# a4989_smoothiebrain_daughterboard.net
KiCad netlist of a schematic drawn in EAGLE
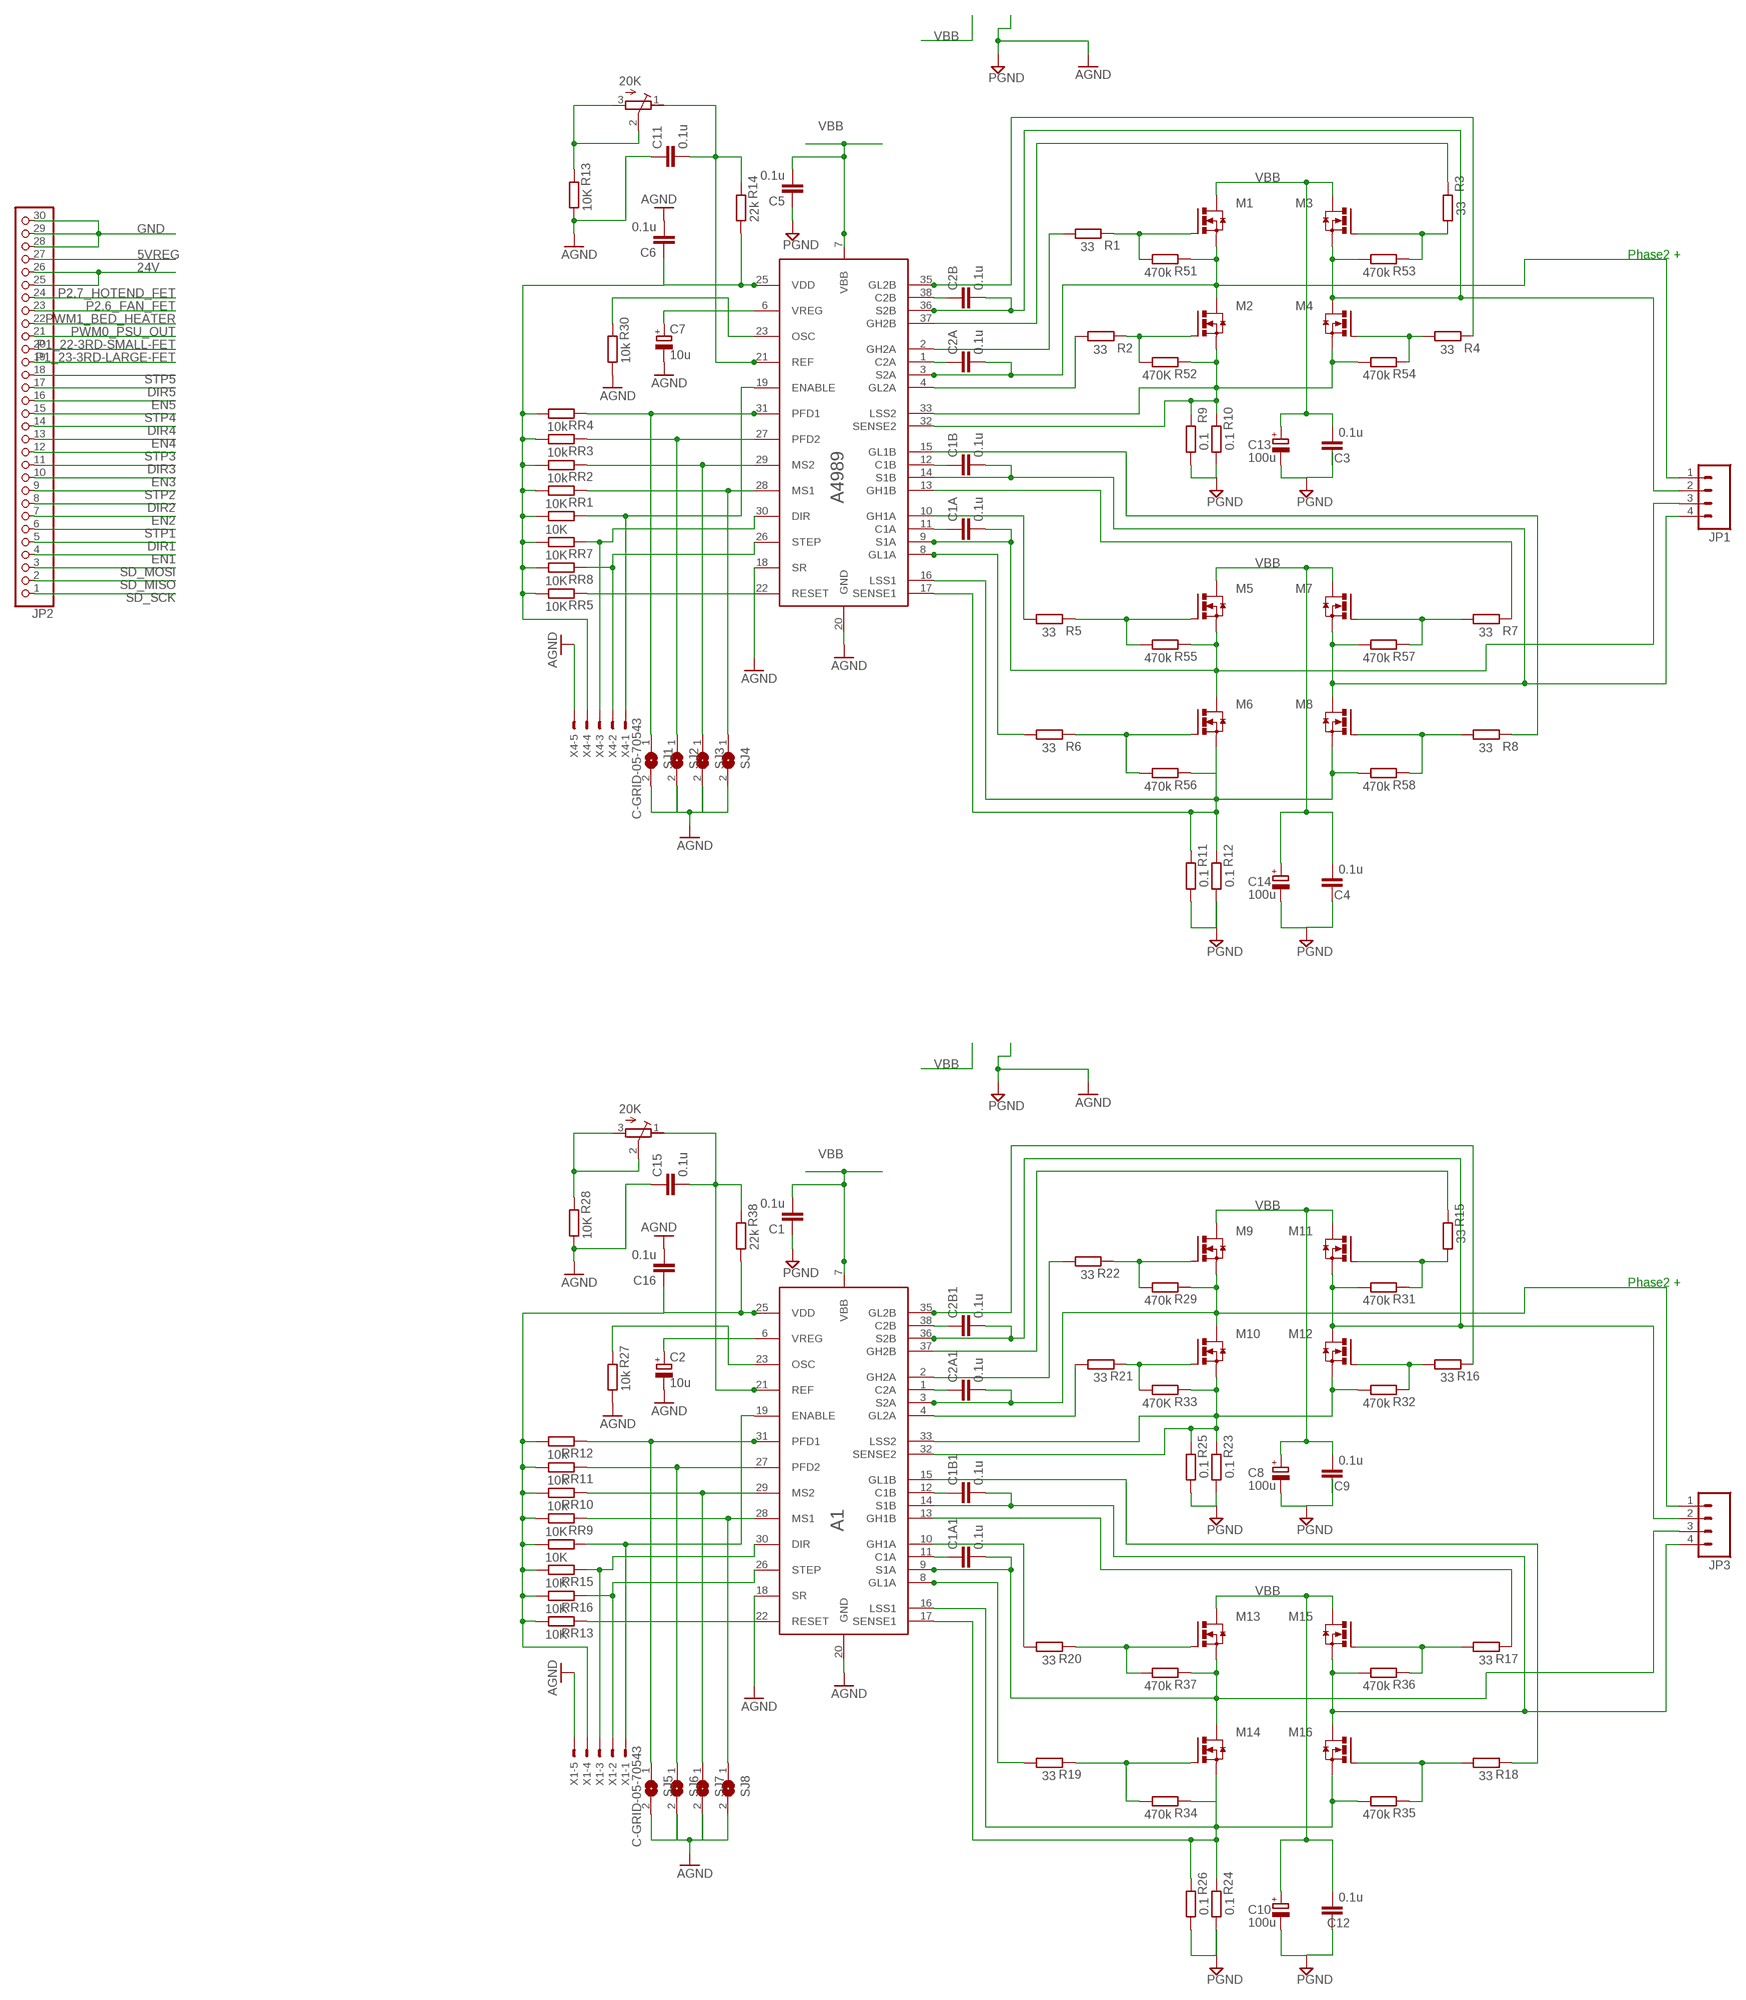
[diagram p0: schematic, sheet 1]

(export (version "E")
  (design (tool "Eeschema 10.0.6"))
  (components
    (comp (ref "A1")
      (value "A4989")
      (footprint "eagle-import:TSSOP39")
      (libsource (lib "eagle-import") (part "A4989"))
    )
    (comp (ref "A4989")
      (value "A4989")
      (footprint "eagle-import:TSSOP39")
      (libsource (lib "eagle-import") (part "A4989"))
    )
    (comp (ref "C1")
      (value "0.1u")
      (footprint "eagle-import:C0603")
      (libsource (lib "eagle-import") (part "C-EUC0603"))
    )
    (comp (ref "C1A")
      (value "0.1u")
      (footprint "eagle-import:C0603")
      (libsource (lib "eagle-import") (part "C-EUC0603"))
    )
    (comp (ref "C1A1")
      (value "0.1u")
      (footprint "eagle-import:C0603")
      (libsource (lib "eagle-import") (part "C-EUC0603"))
    )
    (comp (ref "C1B")
      (value "0.1u")
      (footprint "eagle-import:C0603")
      (libsource (lib "eagle-import") (part "C-EUC0603"))
    )
    (comp (ref "C1B1")
      (value "0.1u")
      (footprint "eagle-import:C0603")
      (libsource (lib "eagle-import") (part "C-EUC0603"))
    )
    (comp (ref "C2")
      (value "10u")
      (footprint "eagle-import:153CLV-0605")
      (libsource (lib "eagle-import") (part "CPOL-EU153CLV-0605"))
    )
    (comp (ref "C2A")
      (value "0.1u")
      (footprint "eagle-import:C0603")
      (libsource (lib "eagle-import") (part "C-EUC0603"))
    )
    (comp (ref "C2A1")
      (value "0.1u")
      (footprint "eagle-import:C0603")
      (libsource (lib "eagle-import") (part "C-EUC0603"))
    )
    (comp (ref "C2B")
      (value "0.1u")
      (footprint "eagle-import:C0603")
      (libsource (lib "eagle-import") (part "C-EUC0603"))
    )
    (comp (ref "C2B1")
      (value "0.1u")
      (footprint "eagle-import:C0603")
      (libsource (lib "eagle-import") (part "C-EUC0603"))
    )
    (comp (ref "C3")
      (value "0.1u")
      (footprint "eagle-import:C0603")
      (libsource (lib "eagle-import") (part "C-EUC0603"))
    )
    (comp (ref "C4")
      (value "0.1u")
      (footprint "eagle-import:C0603")
      (libsource (lib "eagle-import") (part "C-EUC0603"))
    )
    (comp (ref "C5")
      (value "0.1u")
      (footprint "eagle-import:C0603")
      (libsource (lib "eagle-import") (part "C-EUC0603"))
    )
    (comp (ref "C6")
      (value "0.1u")
      (footprint "eagle-import:C0603")
      (libsource (lib "eagle-import") (part "C-EUC0603"))
    )
    (comp (ref "C7")
      (value "10u")
      (footprint "eagle-import:153CLV-0605")
      (libsource (lib "eagle-import") (part "CPOL-EU153CLV-0605"))
    )
    (comp (ref "C8")
      (value "100u")
      (footprint "eagle-import:E5-10,5")
      (libsource (lib "eagle-import") (part "CPOL-EUE5-10.5"))
    )
    (comp (ref "C9")
      (value "0.1u")
      (footprint "eagle-import:C0603")
      (libsource (lib "eagle-import") (part "C-EUC0603"))
    )
    (comp (ref "C10")
      (value "100u")
      (footprint "eagle-import:E5-10,5")
      (libsource (lib "eagle-import") (part "CPOL-EUE5-10.5"))
    )
    (comp (ref "C11")
      (value "0.1u")
      (footprint "eagle-import:C0603")
      (libsource (lib "eagle-import") (part "C-EUC0603"))
    )
    (comp (ref "C12")
      (value "0.1u")
      (footprint "eagle-import:C0603")
      (libsource (lib "eagle-import") (part "C-EUC0603"))
    )
    (comp (ref "C13")
      (value "100u")
      (footprint "eagle-import:E5-10,5")
      (libsource (lib "eagle-import") (part "CPOL-EUE5-10.5"))
    )
    (comp (ref "C14")
      (value "100u")
      (footprint "eagle-import:E5-10,5")
      (libsource (lib "eagle-import") (part "CPOL-EUE5-10.5"))
    )
    (comp (ref "C15")
      (value "0.1u")
      (footprint "eagle-import:C0603")
      (libsource (lib "eagle-import") (part "C-EUC0603"))
    )
    (comp (ref "C16")
      (value "0.1u")
      (footprint "eagle-import:C0603")
      (libsource (lib "eagle-import") (part "C-EUC0603"))
    )
    (comp (ref "JP1")
      (value "M04SCREW")
      (footprint "eagle-import:SCREWTERMINAL-3.5MM-4")
      (libsource (lib "eagle-import") (part "M04SCREW"))
    )
    (comp (ref "JP2")
      (value "PINHD-1X30")
      (footprint "eagle-import:1X30")
      (libsource (lib "eagle-import") (part "PINHD-1X30"))
    )
    (comp (ref "JP3")
      (value "M04SCREW")
      (footprint "eagle-import:SCREWTERMINAL-3.5MM-4")
      (libsource (lib "eagle-import") (part "M04SCREW"))
    )
    (comp (ref "M1")
      (value "IRLR024N")
      (footprint "eagle-import:TO252")
      (libsource (lib "eagle-import") (part "IRLR024N"))
    )
    (comp (ref "M2")
      (value "IRLR024N")
      (footprint "eagle-import:TO252")
      (libsource (lib "eagle-import") (part "IRLR024N"))
    )
    (comp (ref "M3")
      (value "IRLR024N")
      (footprint "eagle-import:TO252")
      (libsource (lib "eagle-import") (part "IRLR024N"))
    )
    (comp (ref "M4")
      (value "IRLR024N")
      (footprint "eagle-import:TO252")
      (libsource (lib "eagle-import") (part "IRLR024N"))
    )
    (comp (ref "M5")
      (value "IRLR024N")
      (footprint "eagle-import:TO252")
      (libsource (lib "eagle-import") (part "IRLR024N"))
    )
    (comp (ref "M6")
      (value "IRLR024N")
      (footprint "eagle-import:TO252")
      (libsource (lib "eagle-import") (part "IRLR024N"))
    )
    (comp (ref "M7")
      (value "IRLR024N")
      (footprint "eagle-import:TO252")
      (libsource (lib "eagle-import") (part "IRLR024N"))
    )
    (comp (ref "M8")
      (value "IRLR024N")
      (footprint "eagle-import:TO252")
      (libsource (lib "eagle-import") (part "IRLR024N"))
    )
    (comp (ref "M9")
      (value "IRLR024N")
      (footprint "eagle-import:TO252")
      (libsource (lib "eagle-import") (part "IRLR024N"))
    )
    (comp (ref "M10")
      (value "IRLR024N")
      (footprint "eagle-import:TO252")
      (libsource (lib "eagle-import") (part "IRLR024N"))
    )
    (comp (ref "M11")
      (value "IRLR024N")
      (footprint "eagle-import:TO252")
      (libsource (lib "eagle-import") (part "IRLR024N"))
    )
    (comp (ref "M12")
      (value "IRLR024N")
      (footprint "eagle-import:TO252")
      (libsource (lib "eagle-import") (part "IRLR024N"))
    )
    (comp (ref "M13")
      (value "IRLR024N")
      (footprint "eagle-import:TO252")
      (libsource (lib "eagle-import") (part "IRLR024N"))
    )
    (comp (ref "M14")
      (value "IRLR024N")
      (footprint "eagle-import:TO252")
      (libsource (lib "eagle-import") (part "IRLR024N"))
    )
    (comp (ref "M15")
      (value "IRLR024N")
      (footprint "eagle-import:TO252")
      (libsource (lib "eagle-import") (part "IRLR024N"))
    )
    (comp (ref "M16")
      (value "IRLR024N")
      (footprint "eagle-import:TO252")
      (libsource (lib "eagle-import") (part "IRLR024N"))
    )
    (comp (ref "R1")
      (value "33")
      (footprint "eagle-import:R0603")
      (libsource (lib "eagle-import") (part "R-EU_R0603"))
    )
    (comp (ref "R2")
      (value "33")
      (footprint "eagle-import:R0603")
      (libsource (lib "eagle-import") (part "R-EU_R0603"))
    )
    (comp (ref "R3")
      (value "33")
      (footprint "eagle-import:R0603")
      (libsource (lib "eagle-import") (part "R-EU_R0603"))
    )
    (comp (ref "R4")
      (value "33")
      (footprint "eagle-import:R0603")
      (libsource (lib "eagle-import") (part "R-EU_R0603"))
    )
    (comp (ref "R5")
      (value "33")
      (footprint "eagle-import:R0603")
      (libsource (lib "eagle-import") (part "R-EU_R0603"))
    )
    (comp (ref "R6")
      (value "33")
      (footprint "eagle-import:R0603")
      (libsource (lib "eagle-import") (part "R-EU_R0603"))
    )
    (comp (ref "R7")
      (value "33")
      (footprint "eagle-import:R0603")
      (libsource (lib "eagle-import") (part "R-EU_R0603"))
    )
    (comp (ref "R8")
      (value "33")
      (footprint "eagle-import:R0603")
      (libsource (lib "eagle-import") (part "R-EU_R0603"))
    )
    (comp (ref "R9")
      (value "0.1")
      (footprint "eagle-import:R2512")
      (libsource (lib "eagle-import") (part "R-EU_R2512"))
    )
    (comp (ref "R10")
      (value "0.1")
      (footprint "eagle-import:R2512")
      (libsource (lib "eagle-import") (part "R-EU_R2512"))
    )
    (comp (ref "R11")
      (value "0.1")
      (footprint "eagle-import:R2512")
      (libsource (lib "eagle-import") (part "R-EU_R2512"))
    )
    (comp (ref "R12")
      (value "0.1")
      (footprint "eagle-import:R2512")
      (libsource (lib "eagle-import") (part "R-EU_R2512"))
    )
    (comp (ref "R13")
      (value "10K")
      (footprint "eagle-import:R0603")
      (libsource (lib "eagle-import") (part "R-EU_R0603"))
    )
    (comp (ref "R14")
      (value "22k")
      (footprint "eagle-import:R0603")
      (libsource (lib "eagle-import") (part "R-EU_R0603"))
    )
    (comp (ref "R15")
      (value "33")
      (footprint "eagle-import:R0603")
      (libsource (lib "eagle-import") (part "R-EU_R0603"))
    )
    (comp (ref "R16")
      (value "33")
      (footprint "eagle-import:R0603")
      (libsource (lib "eagle-import") (part "R-EU_R0603"))
    )
    (comp (ref "R17")
      (value "33")
      (footprint "eagle-import:R0603")
      (libsource (lib "eagle-import") (part "R-EU_R0603"))
    )
    (comp (ref "R18")
      (value "33")
      (footprint "eagle-import:R0603")
      (libsource (lib "eagle-import") (part "R-EU_R0603"))
    )
    (comp (ref "R19")
      (value "33")
      (footprint "eagle-import:R0603")
      (libsource (lib "eagle-import") (part "R-EU_R0603"))
    )
    (comp (ref "R20")
      (value "33")
      (footprint "eagle-import:R0603")
      (libsource (lib "eagle-import") (part "R-EU_R0603"))
    )
    (comp (ref "R21")
      (value "33")
      (footprint "eagle-import:R0603")
      (libsource (lib "eagle-import") (part "R-EU_R0603"))
    )
    (comp (ref "R22")
      (value "33")
      (footprint "eagle-import:R0603")
      (libsource (lib "eagle-import") (part "R-EU_R0603"))
    )
    (comp (ref "R23")
      (value "0.1")
      (footprint "eagle-import:R2512")
      (libsource (lib "eagle-import") (part "R-EU_R2512"))
    )
    (comp (ref "R24")
      (value "0.1")
      (footprint "eagle-import:R2512")
      (libsource (lib "eagle-import") (part "R-EU_R2512"))
    )
    (comp (ref "R25")
      (value "0.1")
      (footprint "eagle-import:R2512")
      (libsource (lib "eagle-import") (part "R-EU_R2512"))
    )
    (comp (ref "R26")
      (value "0.1")
      (footprint "eagle-import:R2512")
      (libsource (lib "eagle-import") (part "R-EU_R2512"))
    )
    (comp (ref "R27")
      (value "10k")
      (footprint "eagle-import:R0603")
      (libsource (lib "eagle-import") (part "R-EU_R0603"))
    )
    (comp (ref "R28")
      (value "10K")
      (footprint "eagle-import:R0603")
      (libsource (lib "eagle-import") (part "R-EU_R0603"))
    )
    (comp (ref "R29")
      (value "470k")
      (footprint "eagle-import:R0603")
      (libsource (lib "eagle-import") (part "R-EU_R0603"))
    )
    (comp (ref "R30")
      (value "10k")
      (footprint "eagle-import:R0603")
      (libsource (lib "eagle-import") (part "R-EU_R0603"))
    )
    (comp (ref "R31")
      (value "470k")
      (footprint "eagle-import:R0603")
      (libsource (lib "eagle-import") (part "R-EU_R0603"))
    )
    (comp (ref "R32")
      (value "470k")
      (footprint "eagle-import:R0603")
      (libsource (lib "eagle-import") (part "R-EU_R0603"))
    )
    (comp (ref "R33")
      (value "470K")
      (footprint "eagle-import:R0603")
      (libsource (lib "eagle-import") (part "R-EU_R0603"))
    )
    (comp (ref "R34")
      (value "470k")
      (footprint "eagle-import:R0603")
      (libsource (lib "eagle-import") (part "R-EU_R0603"))
    )
    (comp (ref "R35")
      (value "470k")
      (footprint "eagle-import:R0603")
      (libsource (lib "eagle-import") (part "R-EU_R0603"))
    )
    (comp (ref "R36")
      (value "470k")
      (footprint "eagle-import:R0603")
      (libsource (lib "eagle-import") (part "R-EU_R0603"))
    )
    (comp (ref "R37")
      (value "470k")
      (footprint "eagle-import:R0603")
      (libsource (lib "eagle-import") (part "R-EU_R0603"))
    )
    (comp (ref "R38")
      (value "22k")
      (footprint "eagle-import:R0603")
      (libsource (lib "eagle-import") (part "R-EU_R0603"))
    )
    (comp (ref "R51")
      (value "470k")
      (footprint "eagle-import:R0603")
      (libsource (lib "eagle-import") (part "R-EU_R0603"))
    )
    (comp (ref "R52")
      (value "470K")
      (footprint "eagle-import:R0603")
      (libsource (lib "eagle-import") (part "R-EU_R0603"))
    )
    (comp (ref "R53")
      (value "470k")
      (footprint "eagle-import:R0603")
      (libsource (lib "eagle-import") (part "R-EU_R0603"))
    )
    (comp (ref "R54")
      (value "470k")
      (footprint "eagle-import:R0603")
      (libsource (lib "eagle-import") (part "R-EU_R0603"))
    )
    (comp (ref "R55")
      (value "470k")
      (footprint "eagle-import:R0603")
      (libsource (lib "eagle-import") (part "R-EU_R0603"))
    )
    (comp (ref "R56")
      (value "470k")
      (footprint "eagle-import:R0603")
      (libsource (lib "eagle-import") (part "R-EU_R0603"))
    )
    (comp (ref "R57")
      (value "470k")
      (footprint "eagle-import:R0603")
      (libsource (lib "eagle-import") (part "R-EU_R0603"))
    )
    (comp (ref "R58")
      (value "470k")
      (footprint "eagle-import:R0603")
      (libsource (lib "eagle-import") (part "R-EU_R0603"))
    )
    (comp (ref "RR1")
      (value "10K")
      (footprint "eagle-import:R0603")
      (libsource (lib "eagle-import") (part "R-EU_R0603"))
    )
    (comp (ref "RR2")
      (value "10k")
      (footprint "eagle-import:R0603")
      (libsource (lib "eagle-import") (part "R-EU_R0603"))
    )
    (comp (ref "RR3")
      (value "10k")
      (footprint "eagle-import:R0603")
      (libsource (lib "eagle-import") (part "R-EU_R0603"))
    )
    (comp (ref "RR4")
      (value "10k")
      (footprint "eagle-import:R0603")
      (libsource (lib "eagle-import") (part "R-EU_R0603"))
    )
    (comp (ref "RR5")
      (value "10K")
      (footprint "eagle-import:R0603")
      (libsource (lib "eagle-import") (part "R-EU_R0603"))
    )
    (comp (ref "RR6")
      (value "10K")
      (footprint "eagle-import:R0603")
      (libsource (lib "eagle-import") (part "R-EU_R0603"))
    )
    (comp (ref "RR7")
      (value "10K")
      (footprint "eagle-import:R0603")
      (libsource (lib "eagle-import") (part "R-EU_R0603"))
    )
    (comp (ref "RR8")
      (value "10K")
      (footprint "eagle-import:R0603")
      (libsource (lib "eagle-import") (part "R-EU_R0603"))
    )
    (comp (ref "RR9")
      (value "10K")
      (footprint "eagle-import:R0603")
      (libsource (lib "eagle-import") (part "R-EU_R0603"))
    )
    (comp (ref "RR10")
      (value "10k")
      (footprint "eagle-import:R0603")
      (libsource (lib "eagle-import") (part "R-EU_R0603"))
    )
    (comp (ref "RR11")
      (value "10k")
      (footprint "eagle-import:R0603")
      (libsource (lib "eagle-import") (part "R-EU_R0603"))
    )
    (comp (ref "RR12")
      (value "10k")
      (footprint "eagle-import:R0603")
      (libsource (lib "eagle-import") (part "R-EU_R0603"))
    )
    (comp (ref "RR13")
      (value "10K")
      (footprint "eagle-import:R0603")
      (libsource (lib "eagle-import") (part "R-EU_R0603"))
    )
    (comp (ref "RR14")
      (value "10K")
      (footprint "eagle-import:R0603")
      (libsource (lib "eagle-import") (part "R-EU_R0603"))
    )
    (comp (ref "RR15")
      (value "10K")
      (footprint "eagle-import:R0603")
      (libsource (lib "eagle-import") (part "R-EU_R0603"))
    )
    (comp (ref "RR16")
      (value "10K")
      (footprint "eagle-import:R0603")
      (libsource (lib "eagle-import") (part "R-EU_R0603"))
    )
    (comp (ref "SJ1") (value "SJ") (footprint "eagle-import:SJ") (libsource (lib "eagle-import") (part "SJ")))
    (comp (ref "SJ2") (value "SJ") (footprint "eagle-import:SJ") (libsource (lib "eagle-import") (part "SJ")))
    (comp (ref "SJ3") (value "SJ") (footprint "eagle-import:SJ") (libsource (lib "eagle-import") (part "SJ")))
    (comp (ref "SJ4") (value "SJ") (footprint "eagle-import:SJ") (libsource (lib "eagle-import") (part "SJ")))
    (comp (ref "SJ5") (value "SJ") (footprint "eagle-import:SJ") (libsource (lib "eagle-import") (part "SJ")))
    (comp (ref "SJ6") (value "SJ") (footprint "eagle-import:SJ") (libsource (lib "eagle-import") (part "SJ")))
    (comp (ref "SJ7") (value "SJ") (footprint "eagle-import:SJ") (libsource (lib "eagle-import") (part "SJ")))
    (comp (ref "SJ8") (value "SJ") (footprint "eagle-import:SJ") (libsource (lib "eagle-import") (part "SJ")))
    (comp (ref "U$1")
      (value "20K")
      (footprint "eagle-import:BOURNS_3266W")
      (libsource (lib "eagle-import") (part "BOURNS_TRIMMER_3266W"))
    )
    (comp (ref "U$2")
      (value "20K")
      (footprint "eagle-import:BOURNS_3266W")
      (libsource (lib "eagle-import") (part "BOURNS_TRIMMER_3266W"))
    )
    (comp (ref "X1")
      (value "C-GRID-05-70543")
      (footprint "eagle-import:70543-05")
      (libsource (lib "eagle-import") (part "C-GRID-05-70543"))
    )
    (comp (ref "X4")
      (value "C-GRID-05-70543")
      (footprint "eagle-import:70543-05")
      (libsource (lib "eagle-import") (part "C-GRID-05-70543"))
    )
  )
  (nets
    (net (code "1") (name "/5VREG") (class "Default")
      (node (ref "A4989") (pin "25") (pinfunction "VDD_25") (pintype "bidirectional"))
      (node (ref "C6") (pin "1") (pinfunction "1_1") (pintype "passive"))
      (node (ref "JP2") (pin "27") (pinfunction "27_27") (pintype "passive"))
      (node (ref "R14") (pin "2") (pinfunction "2_2") (pintype "passive"))
      (node (ref "RR1") (pin "2") (pinfunction "2_2") (pintype "passive"))
      (node (ref "RR2") (pin "2") (pinfunction "2_2") (pintype "passive"))
      (node (ref "RR3") (pin "2") (pinfunction "2_2") (pintype "passive"))
      (node (ref "RR4") (pin "2") (pinfunction "2_2") (pintype "passive"))
      (node (ref "RR5") (pin "2") (pinfunction "2_2") (pintype "passive"))
      (node (ref "RR6") (pin "2") (pinfunction "2_2") (pintype "passive"))
      (node (ref "RR7") (pin "2") (pinfunction "2_2") (pintype "passive"))
      (node (ref "RR8") (pin "2") (pinfunction "2_2") (pintype "passive"))
      (node (ref "X4") (pin "4") (pinfunction "S_4") (pintype "passive"))
    )
    (net (code "2") (name "/24V") (class "Default")
      (node (ref "JP2") (pin "25") (pinfunction "25_25") (pintype "passive"))
      (node (ref "JP2") (pin "26") (pinfunction "26_26") (pintype "passive"))
    )
    (net (code "3") (name "/DIR1") (class "Default")
      (node (ref "A4989") (pin "30") (pinfunction "DIR_30") (pintype "bidirectional"))
      (node (ref "JP2") (pin "5") (pinfunction "5_5") (pintype "passive"))
      (node (ref "RR7") (pin "1") (pinfunction "1_1") (pintype "passive"))
      (node (ref "X4") (pin "3") (pinfunction "S_3") (pintype "passive"))
    )
    (net (code "4") (name "/DIR2") (class "Default")
      (node (ref "JP2") (pin "8") (pinfunction "8_8") (pintype "passive"))
    )
    (net (code "5") (name "/DIR3") (class "Default")
      (node (ref "JP2") (pin "11") (pinfunction "11_11") (pintype "passive"))
    )
    (net (code "6") (name "/DIR4") (class "Default")
      (node (ref "JP2") (pin "14") (pinfunction "14_14") (pintype "passive"))
    )
    (net (code "7") (name "/DIR5") (class "Default")
      (node (ref "JP2") (pin "17") (pinfunction "17_17") (pintype "passive"))
    )
    (net (code "8") (name "/EN1") (class "Default")
      (node (ref "A4989") (pin "19") (pinfunction "ENABLE_19") (pintype "bidirectional"))
      (node (ref "JP2") (pin "4") (pinfunction "4_4") (pintype "passive"))
      (node (ref "RR6") (pin "1") (pinfunction "1_1") (pintype "passive"))
      (node (ref "X4") (pin "1") (pinfunction "S_1") (pintype "passive"))
    )
    (net (code "9") (name "/EN2") (class "Default")
      (node (ref "JP2") (pin "7") (pinfunction "7_7") (pintype "passive"))
    )
    (net (code "10") (name "/EN3") (class "Default")
      (node (ref "JP2") (pin "10") (pinfunction "10_10") (pintype "passive"))
    )
    (net (code "11") (name "/EN4") (class "Default")
      (node (ref "JP2") (pin "13") (pinfunction "13_13") (pintype "passive"))
    )
    (net (code "12") (name "/EN5") (class "Default")
      (node (ref "JP2") (pin "16") (pinfunction "16_16") (pintype "passive"))
    )
    (net (code "13") (name "/P1_22-3RD-SMALL-FET") (class "Default")
      (node (ref "JP2") (pin "20") (pinfunction "20_20") (pintype "passive"))
    )
    (net (code "14") (name "/P1_23-3RD-LARGE-FET") (class "Default")
      (node (ref "JP2") (pin "19") (pinfunction "19_19") (pintype "passive"))
    )
    (net (code "15") (name "/P2.6_FAN_FET") (class "Default")
      (node (ref "JP2") (pin "23") (pinfunction "23_23") (pintype "passive"))
    )
    (net (code "16") (name "/P2.7_HOTEND_FET") (class "Default")
      (node (ref "JP2") (pin "24") (pinfunction "24_24") (pintype "passive"))
    )
    (net (code "17") (name "/PWM0_PSU_OUT") (class "Default")
      (node (ref "JP2") (pin "21") (pinfunction "21_21") (pintype "passive"))
    )
    (net (code "18") (name "/PWM1_BED_HEATER") (class "Default")
      (node (ref "JP2") (pin "22") (pinfunction "22_22") (pintype "passive"))
    )
    (net (code "19") (name "/SD_MISO") (class "Default")
      (node (ref "JP2") (pin "2") (pinfunction "2_2") (pintype "passive"))
    )
    (net (code "20") (name "/SD_MOSI") (class "Default")
      (node (ref "JP2") (pin "3") (pinfunction "3_3") (pintype "passive"))
    )
    (net (code "21") (name "/SD_SCK") (class "Default")
      (node (ref "JP2") (pin "1") (pinfunction "1_1") (pintype "passive"))
    )
    (net (code "22") (name "/STP1") (class "Default")
      (node (ref "A4989") (pin "26") (pinfunction "STEP_26") (pintype "bidirectional"))
      (node (ref "JP2") (pin "6") (pinfunction "6_6") (pintype "passive"))
      (node (ref "RR8") (pin "1") (pinfunction "1_1") (pintype "passive"))
      (node (ref "X4") (pin "2") (pinfunction "S_2") (pintype "passive"))
    )
    (net (code "23") (name "/STP2") (class "Default")
      (node (ref "JP2") (pin "9") (pinfunction "9_9") (pintype "passive"))
    )
    (net (code "24") (name "/STP3") (class "Default")
      (node (ref "JP2") (pin "12") (pinfunction "12_12") (pintype "passive"))
    )
    (net (code "25") (name "/STP4") (class "Default")
      (node (ref "JP2") (pin "15") (pinfunction "15_15") (pintype "passive"))
    )
    (net (code "26") (name "/STP5") (class "Default")
      (node (ref "JP2") (pin "18") (pinfunction "18_18") (pintype "passive"))
    )
    (net (code "27") (name "/VBB") (class "Default")
      (node (ref "A1") (pin "7") (pinfunction "VBB_7") (pintype "bidirectional"))
      (node (ref "A4989") (pin "7") (pinfunction "VBB_7") (pintype "bidirectional"))
      (node (ref "C1") (pin "2") (pinfunction "2_2") (pintype "passive"))
      (node (ref "C10") (pin "+") (pinfunction "+_+") (pintype "passive"))
      (node (ref "C12") (pin "2") (pinfunction "2_2") (pintype "passive"))
      (node (ref "C13") (pin "+") (pinfunction "+_+") (pintype "passive"))
      (node (ref "C14") (pin "+") (pinfunction "+_+") (pintype "passive"))
      (node (ref "C3") (pin "2") (pinfunction "2_2") (pintype "passive"))
      (node (ref "C4") (pin "2") (pinfunction "2_2") (pintype "passive"))
      (node (ref "C5") (pin "2") (pinfunction "2_2") (pintype "passive"))
      (node (ref "C8") (pin "+") (pinfunction "+_+") (pintype "passive"))
      (node (ref "C9") (pin "2") (pinfunction "2_2") (pintype "passive"))
      (node (ref "M1") (pin "3") (pinfunction "D_3") (pintype "passive"))
      (node (ref "M11") (pin "3") (pinfunction "D_3") (pintype "passive"))
      (node (ref "M13") (pin "3") (pinfunction "D_3") (pintype "passive"))
      (node (ref "M15") (pin "3") (pinfunction "D_3") (pintype "passive"))
      (node (ref "M3") (pin "3") (pinfunction "D_3") (pintype "passive"))
      (node (ref "M5") (pin "3") (pinfunction "D_3") (pintype "passive"))
      (node (ref "M7") (pin "3") (pinfunction "D_3") (pintype "passive"))
      (node (ref "M9") (pin "3") (pinfunction "D_3") (pintype "passive"))
    )
    (net (code "28") (name "AGND") (class "Default")
      (node (ref "A1") (pin "18") (pinfunction "SR_18") (pintype "bidirectional"))
      (node (ref "A1") (pin "20") (pinfunction "GND_20") (pintype "bidirectional"))
      (node (ref "A4989") (pin "18") (pinfunction "SR_18") (pintype "bidirectional"))
      (node (ref "A4989") (pin "20") (pinfunction "GND_20") (pintype "bidirectional"))
      (node (ref "C1") (pin "1") (pinfunction "1_1") (pintype "passive"))
      (node (ref "C10") (pin "-") (pinfunction "-_-") (pintype "passive"))
      (node (ref "C11") (pin "1") (pinfunction "1_1") (pintype "passive"))
      (node (ref "C12") (pin "1") (pinfunction "1_1") (pintype "passive"))
      (node (ref "C13") (pin "-") (pinfunction "-_-") (pintype "passive"))
      (node (ref "C14") (pin "-") (pinfunction "-_-") (pintype "passive"))
      (node (ref "C15") (pin "1") (pinfunction "1_1") (pintype "passive"))
      (node (ref "C16") (pin "2") (pinfunction "2_2") (pintype "passive"))
      (node (ref "C2") (pin "-") (pinfunction "-_-") (pintype "passive"))
      (node (ref "C3") (pin "1") (pinfunction "1_1") (pintype "passive"))
      (node (ref "C4") (pin "1") (pinfunction "1_1") (pintype "passive"))
      (node (ref "C5") (pin "1") (pinfunction "1_1") (pintype "passive"))
      (node (ref "C6") (pin "2") (pinfunction "2_2") (pintype "passive"))
      (node (ref "C7") (pin "-") (pinfunction "-_-") (pintype "passive"))
      (node (ref "C8") (pin "-") (pinfunction "-_-") (pintype "passive"))
      (node (ref "C9") (pin "1") (pinfunction "1_1") (pintype "passive"))
      (node (ref "JP2") (pin "28") (pinfunction "28_28") (pintype "passive"))
      (node (ref "JP2") (pin "29") (pinfunction "29_29") (pintype "passive"))
      (node (ref "JP2") (pin "30") (pinfunction "30_30") (pintype "passive"))
      (node (ref "R10") (pin "2") (pinfunction "2_2") (pintype "passive"))
      (node (ref "R11") (pin "2") (pinfunction "2_2") (pintype "passive"))
      (node (ref "R12") (pin "2") (pinfunction "2_2") (pintype "passive"))
      (node (ref "R13") (pin "2") (pinfunction "2_2") (pintype "passive"))
      (node (ref "R23") (pin "2") (pinfunction "2_2") (pintype "passive"))
      (node (ref "R24") (pin "2") (pinfunction "2_2") (pintype "passive"))
      (node (ref "R25") (pin "2") (pinfunction "2_2") (pintype "passive"))
      (node (ref "R26") (pin "2") (pinfunction "2_2") (pintype "passive"))
      (node (ref "R27") (pin "2") (pinfunction "2_2") (pintype "passive"))
      (node (ref "R28") (pin "2") (pinfunction "2_2") (pintype "passive"))
      (node (ref "R30") (pin "2") (pinfunction "2_2") (pintype "passive"))
      (node (ref "R9") (pin "2") (pinfunction "2_2") (pintype "passive"))
      (node (ref "SJ1") (pin "2") (pinfunction "2_2") (pintype "passive"))
      (node (ref "SJ2") (pin "2") (pinfunction "2_2") (pintype "passive"))
      (node (ref "SJ3") (pin "2") (pinfunction "2_2") (pintype "passive"))
      (node (ref "SJ4") (pin "2") (pinfunction "2_2") (pintype "passive"))
      (node (ref "SJ5") (pin "2") (pinfunction "2_2") (pintype "passive"))
      (node (ref "SJ6") (pin "2") (pinfunction "2_2") (pintype "passive"))
      (node (ref "SJ7") (pin "2") (pinfunction "2_2") (pintype "passive"))
      (node (ref "SJ8") (pin "2") (pinfunction "2_2") (pintype "passive"))
      (node (ref "X1") (pin "5") (pinfunction "S_5") (pintype "passive"))
      (node (ref "X4") (pin "5") (pinfunction "S_5") (pintype "passive"))
    )
    (net (code "29") (name "Net-(A1-C1A)") (class "Default")
      (node (ref "A1") (pin "11") (pinfunction "C1A_11") (pintype "bidirectional"))
      (node (ref "C1A1") (pin "1") (pinfunction "1_1") (pintype "passive"))
    )
    (net (code "30") (name "Net-(A1-C1B)") (class "Default")
      (node (ref "A1") (pin "12") (pinfunction "C1B_12") (pintype "bidirectional"))
      (node (ref "C1B1") (pin "1") (pinfunction "1_1") (pintype "passive"))
    )
    (net (code "31") (name "Net-(A1-C2A)") (class "Default")
      (node (ref "A1") (pin "1") (pinfunction "C2A_1") (pintype "bidirectional"))
      (node (ref "C2A1") (pin "1") (pinfunction "1_1") (pintype "passive"))
    )
    (net (code "32") (name "Net-(A1-C2B)") (class "Default")
      (node (ref "A1") (pin "38") (pinfunction "C2B_38") (pintype "bidirectional"))
      (node (ref "C2B1") (pin "1") (pinfunction "1_1") (pintype "passive"))
    )
    (net (code "33") (name "Net-(A1-DIR)") (class "Default")
      (node (ref "A1") (pin "30") (pinfunction "DIR_30") (pintype "bidirectional"))
      (node (ref "RR15") (pin "1") (pinfunction "1_1") (pintype "passive"))
      (node (ref "X1") (pin "3") (pinfunction "S_3") (pintype "passive"))
    )
    (net (code "34") (name "Net-(A1-ENABLE)") (class "Default")
      (node (ref "A1") (pin "19") (pinfunction "ENABLE_19") (pintype "bidirectional"))
      (node (ref "RR14") (pin "1") (pinfunction "1_1") (pintype "passive"))
      (node (ref "X1") (pin "1") (pinfunction "S_1") (pintype "passive"))
    )
    (net (code "35") (name "Net-(A1-GH1A)") (class "Default")
      (node (ref "A1") (pin "10") (pinfunction "GH1A_10") (pintype "bidirectional"))
      (node (ref "R20") (pin "2") (pinfunction "2_2") (pintype "passive"))
    )
    (net (code "36") (name "Net-(A1-GH1B)") (class "Default")
      (node (ref "A1") (pin "13") (pinfunction "GH1B_13") (pintype "bidirectional"))
      (node (ref "R17") (pin "1") (pinfunction "1_1") (pintype "passive"))
    )
    (net (code "37") (name "Net-(A1-GH2A)") (class "Default")
      (node (ref "A1") (pin "2") (pinfunction "GH2A_2") (pintype "bidirectional"))
      (node (ref "R22") (pin "2") (pinfunction "2_2") (pintype "passive"))
    )
    (net (code "38") (name "Net-(A1-GH2B)") (class "Default")
      (node (ref "A1") (pin "37") (pinfunction "GH2B_37") (pintype "bidirectional"))
      (node (ref "R15") (pin "1") (pinfunction "1_1") (pintype "passive"))
    )
    (net (code "39") (name "Net-(A1-GL1A)") (class "Default")
      (node (ref "A1") (pin "8") (pinfunction "GL1A_8") (pintype "bidirectional"))
      (node (ref "R19") (pin "2") (pinfunction "2_2") (pintype "passive"))
    )
    (net (code "40") (name "Net-(A1-GL1B)") (class "Default")
      (node (ref "A1") (pin "15") (pinfunction "GL1B_15") (pintype "bidirectional"))
      (node (ref "R18") (pin "1") (pinfunction "1_1") (pintype "passive"))
    )
    (net (code "41") (name "Net-(A1-GL2A)") (class "Default")
      (node (ref "A1") (pin "4") (pinfunction "GL2A_4") (pintype "bidirectional"))
      (node (ref "R21") (pin "2") (pinfunction "2_2") (pintype "passive"))
    )
    (net (code "42") (name "Net-(A1-GL2B)") (class "Default")
      (node (ref "A1") (pin "35") (pinfunction "GL2B_35") (pintype "bidirectional"))
      (node (ref "R16") (pin "1") (pinfunction "1_1") (pintype "passive"))
    )
    (net (code "43") (name "Net-(A1-LSS1)") (class "Default")
      (node (ref "A1") (pin "16") (pinfunction "LSS1_16") (pintype "bidirectional"))
      (node (ref "A1") (pin "17") (pinfunction "SENSE1_17") (pintype "bidirectional"))
      (node (ref "M14") (pin "2") (pinfunction "S_2") (pintype "passive"))
      (node (ref "M16") (pin "2") (pinfunction "S_2") (pintype "passive"))
      (node (ref "R24") (pin "1") (pinfunction "1_1") (pintype "passive"))
      (node (ref "R26") (pin "1") (pinfunction "1_1") (pintype "passive"))
      (node (ref "R34") (pin "1") (pinfunction "1_1") (pintype "passive"))
      (node (ref "R35") (pin "2") (pinfunction "2_2") (pintype "passive"))
    )
    (net (code "44") (name "Net-(A1-LSS2)") (class "Default")
      (node (ref "A1") (pin "32") (pinfunction "SENSE2_32") (pintype "bidirectional"))
      (node (ref "A1") (pin "33") (pinfunction "LSS2_33") (pintype "bidirectional"))
      (node (ref "M10") (pin "2") (pinfunction "S_2") (pintype "passive"))
      (node (ref "M12") (pin "2") (pinfunction "S_2") (pintype "passive"))
      (node (ref "R23") (pin "1") (pinfunction "1_1") (pintype "passive"))
      (node (ref "R25") (pin "1") (pinfunction "1_1") (pintype "passive"))
      (node (ref "R32") (pin "2") (pinfunction "2_2") (pintype "passive"))
      (node (ref "R33") (pin "1") (pinfunction "1_1") (pintype "passive"))
    )
    (net (code "45") (name "Net-(A1-MS1)") (class "Default")
      (node (ref "A1") (pin "28") (pinfunction "MS1_28") (pintype "bidirectional"))
      (node (ref "RR9") (pin "1") (pinfunction "1_1") (pintype "passive"))
      (node (ref "SJ8") (pin "1") (pinfunction "1_1") (pintype "passive"))
    )
    (net (code "46") (name "Net-(A1-MS2)") (class "Default")
      (node (ref "A1") (pin "29") (pinfunction "MS2_29") (pintype "bidirectional"))
      (node (ref "RR10") (pin "1") (pinfunction "1_1") (pintype "passive"))
      (node (ref "SJ7") (pin "1") (pinfunction "1_1") (pintype "passive"))
    )
    (net (code "47") (name "Net-(A1-OSC)") (class "Default")
      (node (ref "A1") (pin "23") (pinfunction "OSC_23") (pintype "bidirectional"))
      (node (ref "R27") (pin "1") (pinfunction "1_1") (pintype "passive"))
    )
    (net (code "48") (name "Net-(A1-PFD1)") (class "Default")
      (node (ref "A1") (pin "31") (pinfunction "PFD1_31") (pintype "bidirectional"))
      (node (ref "RR12") (pin "1") (pinfunction "1_1") (pintype "passive"))
      (node (ref "SJ5") (pin "1") (pinfunction "1_1") (pintype "passive"))
    )
    (net (code "49") (name "Net-(A1-PFD2)") (class "Default")
      (node (ref "A1") (pin "27") (pinfunction "PFD2_27") (pintype "bidirectional"))
      (node (ref "RR11") (pin "1") (pinfunction "1_1") (pintype "passive"))
      (node (ref "SJ6") (pin "1") (pinfunction "1_1") (pintype "passive"))
    )
    (net (code "50") (name "Net-(A1-REF)") (class "Default")
      (node (ref "A1") (pin "21") (pinfunction "REF_21") (pintype "bidirectional"))
      (node (ref "C15") (pin "2") (pinfunction "2_2") (pintype "passive"))
      (node (ref "R38") (pin "1") (pinfunction "1_1") (pintype "passive"))
      (node (ref "U$2") (pin "1") (pinfunction "A_1") (pintype "passive"))
    )
    (net (code "51") (name "Net-(A1-RESET)") (class "Default")
      (node (ref "A1") (pin "22") (pinfunction "RESET_22") (pintype "bidirectional"))
      (node (ref "RR13") (pin "1") (pinfunction "1_1") (pintype "passive"))
    )
    (net (code "52") (name "Net-(A1-S1A)") (class "Default")
      (node (ref "A1") (pin "9") (pinfunction "S1A_9") (pintype "bidirectional"))
      (node (ref "C1A1") (pin "2") (pinfunction "2_2") (pintype "passive"))
      (node (ref "JP3") (pin "3") (pinfunction "3_3") (pintype "passive"))
      (node (ref "M13") (pin "2") (pinfunction "S_2") (pintype "passive"))
      (node (ref "M14") (pin "3") (pinfunction "D_3") (pintype "passive"))
      (node (ref "R37") (pin "1") (pinfunction "1_1") (pintype "passive"))
    )
    (net (code "53") (name "Net-(A1-S1B)") (class "Default")
      (node (ref "A1") (pin "14") (pinfunction "S1B_14") (pintype "bidirectional"))
      (node (ref "C1B1") (pin "2") (pinfunction "2_2") (pintype "passive"))
      (node (ref "JP3") (pin "4") (pinfunction "4_4") (pintype "passive"))
      (node (ref "M15") (pin "2") (pinfunction "S_2") (pintype "passive"))
      (node (ref "M16") (pin "3") (pinfunction "D_3") (pintype "passive"))
      (node (ref "R36") (pin "2") (pinfunction "2_2") (pintype "passive"))
    )
    (net (code "54") (name "Net-(A1-S2A)") (class "Default")
      (node (ref "A1") (pin "3") (pinfunction "S2A_3") (pintype "bidirectional"))
      (node (ref "C2A1") (pin "2") (pinfunction "2_2") (pintype "passive"))
      (node (ref "JP3") (pin "1") (pinfunction "1_1") (pintype "passive"))
      (node (ref "M10") (pin "3") (pinfunction "D_3") (pintype "passive"))
      (node (ref "M9") (pin "2") (pinfunction "S_2") (pintype "passive"))
      (node (ref "R29") (pin "1") (pinfunction "1_1") (pintype "passive"))
    )
    (net (code "55") (name "Net-(A1-S2B)") (class "Default")
      (node (ref "A1") (pin "36") (pinfunction "S2B_36") (pintype "bidirectional"))
      (node (ref "C2B1") (pin "2") (pinfunction "2_2") (pintype "passive"))
      (node (ref "JP3") (pin "2") (pinfunction "2_2") (pintype "passive"))
      (node (ref "M11") (pin "2") (pinfunction "S_2") (pintype "passive"))
      (node (ref "M12") (pin "3") (pinfunction "D_3") (pintype "passive"))
      (node (ref "R31") (pin "2") (pinfunction "2_2") (pintype "passive"))
    )
    (net (code "56") (name "Net-(A1-STEP)") (class "Default")
      (node (ref "A1") (pin "26") (pinfunction "STEP_26") (pintype "bidirectional"))
      (node (ref "RR16") (pin "1") (pinfunction "1_1") (pintype "passive"))
      (node (ref "X1") (pin "2") (pinfunction "S_2") (pintype "passive"))
    )
    (net (code "57") (name "Net-(A1-VDD)") (class "Default")
      (node (ref "A1") (pin "25") (pinfunction "VDD_25") (pintype "bidirectional"))
      (node (ref "C16") (pin "1") (pinfunction "1_1") (pintype "passive"))
      (node (ref "R38") (pin "2") (pinfunction "2_2") (pintype "passive"))
      (node (ref "RR10") (pin "2") (pinfunction "2_2") (pintype "passive"))
      (node (ref "RR11") (pin "2") (pinfunction "2_2") (pintype "passive"))
      (node (ref "RR12") (pin "2") (pinfunction "2_2") (pintype "passive"))
      (node (ref "RR13") (pin "2") (pinfunction "2_2") (pintype "passive"))
      (node (ref "RR14") (pin "2") (pinfunction "2_2") (pintype "passive"))
      (node (ref "RR15") (pin "2") (pinfunction "2_2") (pintype "passive"))
      (node (ref "RR16") (pin "2") (pinfunction "2_2") (pintype "passive"))
      (node (ref "RR9") (pin "2") (pinfunction "2_2") (pintype "passive"))
      (node (ref "X1") (pin "4") (pinfunction "S_4") (pintype "passive"))
    )
    (net (code "58") (name "Net-(A1-VREG)") (class "Default")
      (node (ref "A1") (pin "6") (pinfunction "VREG_6") (pintype "bidirectional"))
      (node (ref "C2") (pin "+") (pinfunction "+_+") (pintype "passive"))
    )
    (net (code "59") (name "Net-(A4989-C1A)") (class "Default")
      (node (ref "A4989") (pin "11") (pinfunction "C1A_11") (pintype "bidirectional"))
      (node (ref "C1A") (pin "1") (pinfunction "1_1") (pintype "passive"))
    )
    (net (code "60") (name "Net-(A4989-C1B)") (class "Default")
      (node (ref "A4989") (pin "12") (pinfunction "C1B_12") (pintype "bidirectional"))
      (node (ref "C1B") (pin "1") (pinfunction "1_1") (pintype "passive"))
    )
    (net (code "61") (name "Net-(A4989-C2A)") (class "Default")
      (node (ref "A4989") (pin "1") (pinfunction "C2A_1") (pintype "bidirectional"))
      (node (ref "C2A") (pin "1") (pinfunction "1_1") (pintype "passive"))
    )
    (net (code "62") (name "Net-(A4989-C2B)") (class "Default")
      (node (ref "A4989") (pin "38") (pinfunction "C2B_38") (pintype "bidirectional"))
      (node (ref "C2B") (pin "1") (pinfunction "1_1") (pintype "passive"))
    )
    (net (code "63") (name "Net-(A4989-GH1A)") (class "Default")
      (node (ref "A4989") (pin "10") (pinfunction "GH1A_10") (pintype "bidirectional"))
      (node (ref "R5") (pin "2") (pinfunction "2_2") (pintype "passive"))
    )
    (net (code "64") (name "Net-(A4989-GH1B)") (class "Default")
      (node (ref "A4989") (pin "13") (pinfunction "GH1B_13") (pintype "bidirectional"))
      (node (ref "R7") (pin "1") (pinfunction "1_1") (pintype "passive"))
    )
    (net (code "65") (name "Net-(A4989-GH2A)") (class "Default")
      (node (ref "A4989") (pin "2") (pinfunction "GH2A_2") (pintype "bidirectional"))
      (node (ref "R1") (pin "2") (pinfunction "2_2") (pintype "passive"))
    )
    (net (code "66") (name "Net-(A4989-GH2B)") (class "Default")
      (node (ref "A4989") (pin "37") (pinfunction "GH2B_37") (pintype "bidirectional"))
      (node (ref "R3") (pin "1") (pinfunction "1_1") (pintype "passive"))
    )
    (net (code "67") (name "Net-(A4989-GL1A)") (class "Default")
      (node (ref "A4989") (pin "8") (pinfunction "GL1A_8") (pintype "bidirectional"))
      (node (ref "R6") (pin "2") (pinfunction "2_2") (pintype "passive"))
    )
    (net (code "68") (name "Net-(A4989-GL1B)") (class "Default")
      (node (ref "A4989") (pin "15") (pinfunction "GL1B_15") (pintype "bidirectional"))
      (node (ref "R8") (pin "1") (pinfunction "1_1") (pintype "passive"))
    )
    (net (code "69") (name "Net-(A4989-GL2A)") (class "Default")
      (node (ref "A4989") (pin "4") (pinfunction "GL2A_4") (pintype "bidirectional"))
      (node (ref "R2") (pin "2") (pinfunction "2_2") (pintype "passive"))
    )
    (net (code "70") (name "Net-(A4989-GL2B)") (class "Default")
      (node (ref "A4989") (pin "35") (pinfunction "GL2B_35") (pintype "bidirectional"))
      (node (ref "R4") (pin "1") (pinfunction "1_1") (pintype "passive"))
    )
    (net (code "71") (name "Net-(A4989-LSS1)") (class "Default")
      (node (ref "A4989") (pin "16") (pinfunction "LSS1_16") (pintype "bidirectional"))
      (node (ref "A4989") (pin "17") (pinfunction "SENSE1_17") (pintype "bidirectional"))
      (node (ref "M6") (pin "2") (pinfunction "S_2") (pintype "passive"))
      (node (ref "M8") (pin "2") (pinfunction "S_2") (pintype "passive"))
      (node (ref "R11") (pin "1") (pinfunction "1_1") (pintype "passive"))
      (node (ref "R12") (pin "1") (pinfunction "1_1") (pintype "passive"))
      (node (ref "R56") (pin "1") (pinfunction "1_1") (pintype "passive"))
      (node (ref "R58") (pin "2") (pinfunction "2_2") (pintype "passive"))
    )
    (net (code "72") (name "Net-(A4989-LSS2)") (class "Default")
      (node (ref "A4989") (pin "32") (pinfunction "SENSE2_32") (pintype "bidirectional"))
      (node (ref "A4989") (pin "33") (pinfunction "LSS2_33") (pintype "bidirectional"))
      (node (ref "M2") (pin "2") (pinfunction "S_2") (pintype "passive"))
      (node (ref "M4") (pin "2") (pinfunction "S_2") (pintype "passive"))
      (node (ref "R10") (pin "1") (pinfunction "1_1") (pintype "passive"))
      (node (ref "R52") (pin "1") (pinfunction "1_1") (pintype "passive"))
      (node (ref "R54") (pin "2") (pinfunction "2_2") (pintype "passive"))
      (node (ref "R9") (pin "1") (pinfunction "1_1") (pintype "passive"))
    )
    (net (code "73") (name "Net-(A4989-MS1)") (class "Default")
      (node (ref "A4989") (pin "28") (pinfunction "MS1_28") (pintype "bidirectional"))
      (node (ref "RR1") (pin "1") (pinfunction "1_1") (pintype "passive"))
      (node (ref "SJ4") (pin "1") (pinfunction "1_1") (pintype "passive"))
    )
    (net (code "74") (name "Net-(A4989-MS2)") (class "Default")
      (node (ref "A4989") (pin "29") (pinfunction "MS2_29") (pintype "bidirectional"))
      (node (ref "RR2") (pin "1") (pinfunction "1_1") (pintype "passive"))
      (node (ref "SJ3") (pin "1") (pinfunction "1_1") (pintype "passive"))
    )
    (net (code "75") (name "Net-(A4989-OSC)") (class "Default")
      (node (ref "A4989") (pin "23") (pinfunction "OSC_23") (pintype "bidirectional"))
      (node (ref "R30") (pin "1") (pinfunction "1_1") (pintype "passive"))
    )
    (net (code "76") (name "Net-(A4989-PFD1)") (class "Default")
      (node (ref "A4989") (pin "31") (pinfunction "PFD1_31") (pintype "bidirectional"))
      (node (ref "RR4") (pin "1") (pinfunction "1_1") (pintype "passive"))
      (node (ref "SJ1") (pin "1") (pinfunction "1_1") (pintype "passive"))
    )
    (net (code "77") (name "Net-(A4989-PFD2)") (class "Default")
      (node (ref "A4989") (pin "27") (pinfunction "PFD2_27") (pintype "bidirectional"))
      (node (ref "RR3") (pin "1") (pinfunction "1_1") (pintype "passive"))
      (node (ref "SJ2") (pin "1") (pinfunction "1_1") (pintype "passive"))
    )
    (net (code "78") (name "Net-(A4989-REF)") (class "Default")
      (node (ref "A4989") (pin "21") (pinfunction "REF_21") (pintype "bidirectional"))
      (node (ref "C11") (pin "2") (pinfunction "2_2") (pintype "passive"))
      (node (ref "R14") (pin "1") (pinfunction "1_1") (pintype "passive"))
      (node (ref "U$1") (pin "1") (pinfunction "A_1") (pintype "passive"))
    )
    (net (code "79") (name "Net-(A4989-RESET)") (class "Default")
      (node (ref "A4989") (pin "22") (pinfunction "RESET_22") (pintype "bidirectional"))
      (node (ref "RR5") (pin "1") (pinfunction "1_1") (pintype "passive"))
    )
    (net (code "80") (name "Net-(A4989-S1A)") (class "Default")
      (node (ref "A4989") (pin "9") (pinfunction "S1A_9") (pintype "bidirectional"))
      (node (ref "C1A") (pin "2") (pinfunction "2_2") (pintype "passive"))
      (node (ref "JP1") (pin "3") (pinfunction "3_3") (pintype "passive"))
      (node (ref "M5") (pin "2") (pinfunction "S_2") (pintype "passive"))
      (node (ref "M6") (pin "3") (pinfunction "D_3") (pintype "passive"))
      (node (ref "R55") (pin "1") (pinfunction "1_1") (pintype "passive"))
    )
    (net (code "81") (name "Net-(A4989-S1B)") (class "Default")
      (node (ref "A4989") (pin "14") (pinfunction "S1B_14") (pintype "bidirectional"))
      (node (ref "C1B") (pin "2") (pinfunction "2_2") (pintype "passive"))
      (node (ref "JP1") (pin "4") (pinfunction "4_4") (pintype "passive"))
      (node (ref "M7") (pin "2") (pinfunction "S_2") (pintype "passive"))
      (node (ref "M8") (pin "3") (pinfunction "D_3") (pintype "passive"))
      (node (ref "R57") (pin "2") (pinfunction "2_2") (pintype "passive"))
    )
    (net (code "82") (name "Net-(A4989-S2A)") (class "Default")
      (node (ref "A4989") (pin "3") (pinfunction "S2A_3") (pintype "bidirectional"))
      (node (ref "C2A") (pin "2") (pinfunction "2_2") (pintype "passive"))
      (node (ref "JP1") (pin "1") (pinfunction "1_1") (pintype "passive"))
      (node (ref "M1") (pin "2") (pinfunction "S_2") (pintype "passive"))
      (node (ref "M2") (pin "3") (pinfunction "D_3") (pintype "passive"))
      (node (ref "R51") (pin "1") (pinfunction "1_1") (pintype "passive"))
    )
    (net (code "83") (name "Net-(A4989-S2B)") (class "Default")
      (node (ref "A4989") (pin "36") (pinfunction "S2B_36") (pintype "bidirectional"))
      (node (ref "C2B") (pin "2") (pinfunction "2_2") (pintype "passive"))
      (node (ref "JP1") (pin "2") (pinfunction "2_2") (pintype "passive"))
      (node (ref "M3") (pin "2") (pinfunction "S_2") (pintype "passive"))
      (node (ref "M4") (pin "3") (pinfunction "D_3") (pintype "passive"))
      (node (ref "R53") (pin "2") (pinfunction "2_2") (pintype "passive"))
    )
    (net (code "84") (name "Net-(A4989-VREG)") (class "Default")
      (node (ref "A4989") (pin "6") (pinfunction "VREG_6") (pintype "bidirectional"))
      (node (ref "C7") (pin "+") (pinfunction "+_+") (pintype "passive"))
    )
    (net (code "85") (name "Net-(M1-G)") (class "Default")
      (node (ref "M1") (pin "1") (pinfunction "G_1") (pintype "passive"))
      (node (ref "R1") (pin "1") (pinfunction "1_1") (pintype "passive"))
      (node (ref "R51") (pin "2") (pinfunction "2_2") (pintype "passive"))
    )
    (net (code "86") (name "Net-(M2-G)") (class "Default")
      (node (ref "M2") (pin "1") (pinfunction "G_1") (pintype "passive"))
      (node (ref "R2") (pin "1") (pinfunction "1_1") (pintype "passive"))
      (node (ref "R52") (pin "2") (pinfunction "2_2") (pintype "passive"))
    )
    (net (code "87") (name "Net-(M3-G)") (class "Default")
      (node (ref "M3") (pin "1") (pinfunction "G_1") (pintype "passive"))
      (node (ref "R3") (pin "2") (pinfunction "2_2") (pintype "passive"))
      (node (ref "R53") (pin "1") (pinfunction "1_1") (pintype "passive"))
    )
    (net (code "88") (name "Net-(M4-G)") (class "Default")
      (node (ref "M4") (pin "1") (pinfunction "G_1") (pintype "passive"))
      (node (ref "R4") (pin "2") (pinfunction "2_2") (pintype "passive"))
      (node (ref "R54") (pin "1") (pinfunction "1_1") (pintype "passive"))
    )
    (net (code "89") (name "Net-(M5-G)") (class "Default")
      (node (ref "M5") (pin "1") (pinfunction "G_1") (pintype "passive"))
      (node (ref "R5") (pin "1") (pinfunction "1_1") (pintype "passive"))
      (node (ref "R55") (pin "2") (pinfunction "2_2") (pintype "passive"))
    )
    (net (code "90") (name "Net-(M6-G)") (class "Default")
      (node (ref "M6") (pin "1") (pinfunction "G_1") (pintype "passive"))
      (node (ref "R56") (pin "2") (pinfunction "2_2") (pintype "passive"))
      (node (ref "R6") (pin "1") (pinfunction "1_1") (pintype "passive"))
    )
    (net (code "91") (name "Net-(M7-G)") (class "Default")
      (node (ref "M7") (pin "1") (pinfunction "G_1") (pintype "passive"))
      (node (ref "R57") (pin "1") (pinfunction "1_1") (pintype "passive"))
      (node (ref "R7") (pin "2") (pinfunction "2_2") (pintype "passive"))
    )
    (net (code "92") (name "Net-(M8-G)") (class "Default")
      (node (ref "M8") (pin "1") (pinfunction "G_1") (pintype "passive"))
      (node (ref "R58") (pin "1") (pinfunction "1_1") (pintype "passive"))
      (node (ref "R8") (pin "2") (pinfunction "2_2") (pintype "passive"))
    )
    (net (code "93") (name "Net-(M9-G)") (class "Default")
      (node (ref "M9") (pin "1") (pinfunction "G_1") (pintype "passive"))
      (node (ref "R22") (pin "1") (pinfunction "1_1") (pintype "passive"))
      (node (ref "R29") (pin "2") (pinfunction "2_2") (pintype "passive"))
    )
    (net (code "94") (name "Net-(M10-G)") (class "Default")
      (node (ref "M10") (pin "1") (pinfunction "G_1") (pintype "passive"))
      (node (ref "R21") (pin "1") (pinfunction "1_1") (pintype "passive"))
      (node (ref "R33") (pin "2") (pinfunction "2_2") (pintype "passive"))
    )
    (net (code "95") (name "Net-(M11-G)") (class "Default")
      (node (ref "M11") (pin "1") (pinfunction "G_1") (pintype "passive"))
      (node (ref "R15") (pin "2") (pinfunction "2_2") (pintype "passive"))
      (node (ref "R31") (pin "1") (pinfunction "1_1") (pintype "passive"))
    )
    (net (code "96") (name "Net-(M12-G)") (class "Default")
      (node (ref "M12") (pin "1") (pinfunction "G_1") (pintype "passive"))
      (node (ref "R16") (pin "2") (pinfunction "2_2") (pintype "passive"))
      (node (ref "R32") (pin "1") (pinfunction "1_1") (pintype "passive"))
    )
    (net (code "97") (name "Net-(M13-G)") (class "Default")
      (node (ref "M13") (pin "1") (pinfunction "G_1") (pintype "passive"))
      (node (ref "R20") (pin "1") (pinfunction "1_1") (pintype "passive"))
      (node (ref "R37") (pin "2") (pinfunction "2_2") (pintype "passive"))
    )
    (net (code "98") (name "Net-(M14-G)") (class "Default")
      (node (ref "M14") (pin "1") (pinfunction "G_1") (pintype "passive"))
      (node (ref "R19") (pin "1") (pinfunction "1_1") (pintype "passive"))
      (node (ref "R34") (pin "2") (pinfunction "2_2") (pintype "passive"))
    )
    (net (code "99") (name "Net-(M15-G)") (class "Default")
      (node (ref "M15") (pin "1") (pinfunction "G_1") (pintype "passive"))
      (node (ref "R17") (pin "2") (pinfunction "2_2") (pintype "passive"))
      (node (ref "R36") (pin "1") (pinfunction "1_1") (pintype "passive"))
    )
    (net (code "100") (name "Net-(M16-G)") (class "Default")
      (node (ref "M16") (pin "1") (pinfunction "G_1") (pintype "passive"))
      (node (ref "R18") (pin "2") (pinfunction "2_2") (pintype "passive"))
      (node (ref "R35") (pin "1") (pinfunction "1_1") (pintype "passive"))
    )
    (net (code "101") (name "Net-(U$1-E)") (class "Default")
      (node (ref "R13") (pin "1") (pinfunction "1_1") (pintype "passive"))
      (node (ref "U$1") (pin "2") (pinfunction "S_2") (pintype "passive"))
      (node (ref "U$1") (pin "3") (pinfunction "E_3") (pintype "passive"))
    )
    (net (code "102") (name "Net-(U$2-E)") (class "Default")
      (node (ref "R28") (pin "1") (pinfunction "1_1") (pintype "passive"))
      (node (ref "U$2") (pin "2") (pinfunction "S_2") (pintype "passive"))
      (node (ref "U$2") (pin "3") (pinfunction "E_3") (pintype "passive"))
    )
  )
)
